# Battery2.net
KiCad netlist of a schematic drawn in Altium Designer
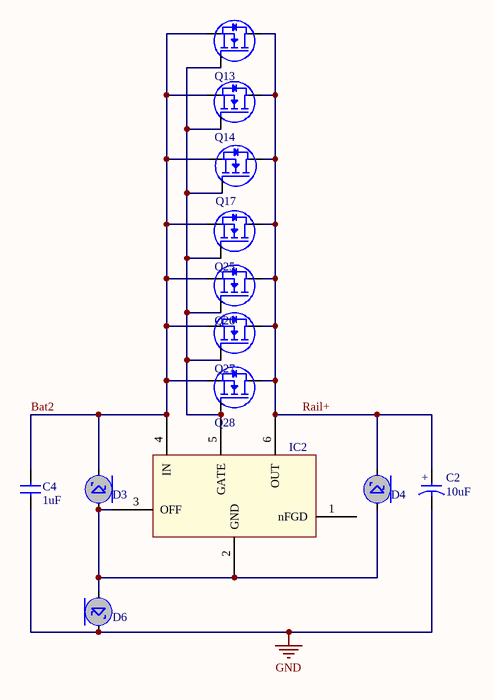
[diagram p0: Battery2.SchDoc]

(export (version "E")
  (design (tool "Eeschema 10.0.6"))
  (components
    (comp (ref "C2")
      (value "10uF")
      (footprint "CAP22uF100V")
      (fields (field (name "Comment") "CapPol"))
      (libsource (lib "SubjuGator8") (part "CapPol"))
    )
    (comp (ref "C4")
      (value "1uF")
      (footprint "CAPC1206")
      (fields (field (name "Comment") "Cap"))
      (libsource (lib "SubjuGator8") (part "Cap"))
    )
    (comp (ref "D3")
      (value "Schottky")
      (footprint "SS110-TP")
      (description "Schottky Diode Template")
      (libsource (lib "SubjuGator8") (part "Schottky"))
    )
    (comp (ref "D4")
      (value "SMBJ100A-13-F")
      (footprint "SMBJ100A-13-F")
      (description "TVS DIODE 100VWM 162VC SMB")
      (libsource (lib "SubjuGator8") (part "SMBJ100A-13-F"))
    )
    (comp (ref "D6")
      (value "Schottky")
      (footprint "SS110-TP")
      (description "Schottky Diode Template")
      (libsource (lib "") (part "Schottky_1"))
    )
    (comp (ref "IC2")
      (value "LM5050MK-2/NOPB")
      (footprint "LM5050MK-2/NOPB")
      (description "IC OR CTRLR N+1 6SOT")
      (libsource (lib "SubjuGator8") (part "LM5050MK-2/NOPB"))
    )
    (comp (ref "Q13")
      (value "CSD19502Q5B")
      (footprint "CSD19502Q5B")
      (description "NEXFET Power MOSFET")
      (libsource (lib "SubjuGator8") (part "CSD19502Q5B"))
    )
    (comp (ref "Q14")
      (value "CSD19502Q5B")
      (footprint "CSD19502Q5B")
      (description "NEXFET Power MOSFET")
      (libsource (lib "SubjuGator8") (part "CSD19502Q5B"))
    )
    (comp (ref "Q17")
      (value "CSD19502Q5B")
      (footprint "CSD19502Q5B")
      (description "NEXFET Power MOSFET")
      (libsource (lib "SubjuGator8") (part "CSD19502Q5B"))
    )
    (comp (ref "Q25")
      (value "CSD19502Q5B")
      (footprint "CSD19502Q5B")
      (description "NEXFET Power MOSFET")
      (libsource (lib "SubjuGator8") (part "CSD19502Q5B"))
    )
    (comp (ref "Q26")
      (value "CSD19502Q5B")
      (footprint "CSD19502Q5B")
      (description "NEXFET Power MOSFET")
      (libsource (lib "SubjuGator8") (part "CSD19502Q5B"))
    )
    (comp (ref "Q27")
      (value "CSD19502Q5B")
      (footprint "CSD19502Q5B")
      (description "NEXFET Power MOSFET")
      (libsource (lib "SubjuGator8") (part "CSD19502Q5B"))
    )
    (comp (ref "Q28")
      (value "CSD19502Q5B")
      (footprint "CSD19502Q5B")
      (description "NEXFET Power MOSFET")
      (libsource (lib "SubjuGator8") (part "CSD19502Q5B"))
    )
  )
  (nets
    (net (code "1") (name "/Bat2") (class "Default")
      (node (ref "C4") (pin "1") (pinfunction "A_1") (pintype "passive"))
      (node (ref "D3") (pin "C") (pinfunction "C_C") (pintype "passive"))
      (node (ref "IC2") (pin "4") (pinfunction "IN_4") (pintype "passive"))
      (node (ref "Q13") (pin "S") (pinfunction "S_S") (pintype "passive"))
      (node (ref "Q14") (pin "S") (pinfunction "S_S") (pintype "passive"))
      (node (ref "Q17") (pin "S") (pinfunction "S_S") (pintype "passive"))
      (node (ref "Q25") (pin "S") (pinfunction "S_S") (pintype "passive"))
      (node (ref "Q26") (pin "S") (pinfunction "S_S") (pintype "passive"))
      (node (ref "Q27") (pin "S") (pinfunction "S_S") (pintype "passive"))
      (node (ref "Q28") (pin "S") (pinfunction "S_S") (pintype "passive"))
    )
    (net (code "2") (name "/Rail+") (class "Default")
      (node (ref "C2") (pin "1") (pinfunction "A_1") (pintype "passive"))
      (node (ref "D4") (pin "C") (pinfunction "C_C") (pintype "passive"))
      (node (ref "IC2") (pin "6") (pinfunction "OUT_6") (pintype "passive"))
      (node (ref "Q13") (pin "D") (pinfunction "D_D") (pintype "passive"))
      (node (ref "Q14") (pin "D") (pinfunction "D_D") (pintype "passive"))
      (node (ref "Q17") (pin "D") (pinfunction "D_D") (pintype "passive"))
      (node (ref "Q25") (pin "D") (pinfunction "D_D") (pintype "passive"))
      (node (ref "Q26") (pin "D") (pinfunction "D_D") (pintype "passive"))
      (node (ref "Q27") (pin "D") (pinfunction "D_D") (pintype "passive"))
      (node (ref "Q28") (pin "D") (pinfunction "D_D") (pintype "passive"))
    )
    (net (code "3") (name "GND") (class "Default")
      (node (ref "C2") (pin "2") (pinfunction "B_2") (pintype "passive"))
      (node (ref "C4") (pin "2") (pinfunction "B_2") (pintype "passive"))
      (node (ref "D6") (pin "C") (pinfunction "C_C") (pintype "passive"))
    )
    (net (code "4") (name "Net-(IC2-GATE)") (class "Default")
      (node (ref "IC2") (pin "5") (pinfunction "GATE_5") (pintype "passive"))
      (node (ref "Q13") (pin "G") (pinfunction "G_G") (pintype "passive"))
      (node (ref "Q14") (pin "G") (pinfunction "G_G") (pintype "passive"))
      (node (ref "Q17") (pin "G") (pinfunction "G_G") (pintype "passive"))
      (node (ref "Q25") (pin "G") (pinfunction "G_G") (pintype "passive"))
      (node (ref "Q26") (pin "G") (pinfunction "G_G") (pintype "passive"))
      (node (ref "Q27") (pin "G") (pinfunction "G_G") (pintype "passive"))
      (node (ref "Q28") (pin "G") (pinfunction "G_G") (pintype "passive"))
    )
    (net (code "5") (name "Net-(IC2-GND)") (class "Default")
      (node (ref "D3") (pin "A") (pinfunction "A_A") (pintype "passive"))
      (node (ref "D4") (pin "A") (pinfunction "A_A") (pintype "passive"))
      (node (ref "D6") (pin "A") (pinfunction "A_A") (pintype "passive"))
      (node (ref "IC2") (pin "2") (pinfunction "GND_2") (pintype "passive"))
      (node (ref "IC2") (pin "3") (pinfunction "OFF_3") (pintype "passive"))
    )
    (net (code "6") (name "unconnected-(IC2-nFGD-Pad1)") (class "Default")
      (node (ref "IC2") (pin "1") (pinfunction "nFGD_1") (pintype "passive"))
    )
  )
)
